# DUAL_CHANNEL_REAY_DRIVER.net
KiCad netlist of a schematic drawn in EAGLE
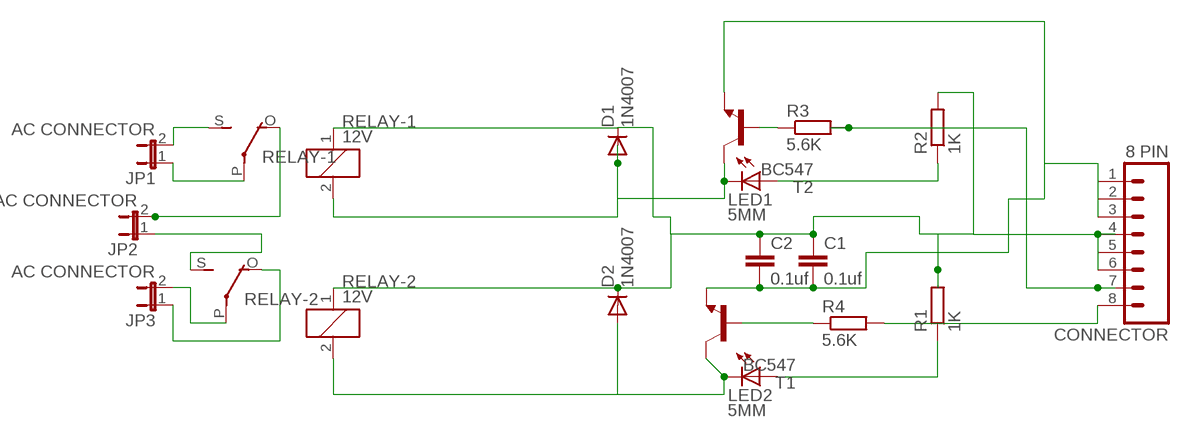
[diagram p0: schematic, sheet 1]

(export (version "E")
  (design (tool "Eeschema 10.0.6"))
  (components
    (comp (ref "C1")
      (value "0.1uf")
      (footprint "eagle-import:C2.5-3")
      (libsource (lib "eagle-import") (part "C2,5-3"))
    )
    (comp (ref "C2")
      (value "0.1uf")
      (footprint "eagle-import:C2.5-3")
      (libsource (lib "eagle-import") (part "C2,5-3"))
    )
    (comp (ref "CONNECTOR")
      (value "8 PIN")
      (footprint "eagle-import:08P")
      (libsource (lib "eagle-import") (part "M08"))
    )
    (comp (ref "D1")
      (value "1N4007")
      (footprint "eagle-import:DO41-10")
      (libsource (lib "eagle-import") (part "1N4004"))
    )
    (comp (ref "D2")
      (value "1N4007")
      (footprint "eagle-import:DO41-10")
      (libsource (lib "eagle-import") (part "1N4004"))
    )
    (comp (ref "JP1")
      (value "AC CONNECTOR")
      (footprint "eagle-import:JP1")
      (libsource (lib "eagle-import") (part "JP1E"))
    )
    (comp (ref "JP2")
      (value "AC CONNECTOR")
      (footprint "eagle-import:JP1")
      (libsource (lib "eagle-import") (part "JP1E"))
    )
    (comp (ref "JP3")
      (value "AC CONNECTOR")
      (footprint "eagle-import:JP1")
      (libsource (lib "eagle-import") (part "JP1E"))
    )
    (comp (ref "LED1")
      (value "5MM")
      (footprint "eagle-import:LED5MM")
      (libsource (lib "eagle-import") (part "LED5MM"))
    )
    (comp (ref "LED2")
      (value "5MM")
      (footprint "eagle-import:LED5MM")
      (libsource (lib "eagle-import") (part "LED5MM"))
    )
    (comp (ref "R1")
      (value "1K")
      (footprint "eagle-import:0204_7")
      (libsource (lib "eagle-import") (part "R-EU_0204/7"))
    )
    (comp (ref "R2")
      (value "1K")
      (footprint "eagle-import:0204_7")
      (libsource (lib "eagle-import") (part "R-EU_0204/7"))
    )
    (comp (ref "R3")
      (value "5.6K")
      (footprint "eagle-import:0204_7")
      (libsource (lib "eagle-import") (part "R-EU_0204/7"))
    )
    (comp (ref "R4")
      (value "5.6K")
      (footprint "eagle-import:0204_7")
      (libsource (lib "eagle-import") (part "R-EU_0204/7"))
    )
    (comp (ref "RELAY-1")
      (value "12V")
      (footprint "eagle-import:G5LE")
      (libsource (lib "eagle-import") (part "G5L"))
    )
    (comp (ref "RELAY-2")
      (value "12V")
      (footprint "eagle-import:G5LE")
      (libsource (lib "eagle-import") (part "G5L"))
    )
    (comp (ref "T1")
      (value "BC547")
      (footprint "eagle-import:TO92")
      (libsource (lib "eagle-import") (part "BC547"))
    )
    (comp (ref "T2")
      (value "BC547")
      (footprint "eagle-import:TO92")
      (libsource (lib "eagle-import") (part "BC547"))
    )
  )
  (nets
    (net (code "1") (name "Net-(C1-Pad1)") (class "Default")
      (node (ref "C1") (pin "1") (pinfunction "1_1") (pintype "passive"))
      (node (ref "C2") (pin "1") (pinfunction "1_1") (pintype "passive"))
      (node (ref "CONNECTOR") (pin "4") (pinfunction "4_4") (pintype "passive"))
      (node (ref "CONNECTOR") (pin "5") (pinfunction "5_5") (pintype "passive"))
      (node (ref "CONNECTOR") (pin "6") (pinfunction "6_6") (pintype "passive"))
      (node (ref "D1") (pin "C") (pinfunction "C_C") (pintype "passive"))
      (node (ref "D2") (pin "C") (pinfunction "C_C") (pintype "passive"))
      (node (ref "R1") (pin "2") (pinfunction "2_2") (pintype "passive"))
      (node (ref "R2") (pin "2") (pinfunction "2_2") (pintype "passive"))
      (node (ref "RELAY-1") (pin "1") (pinfunction "1_1") (pintype "passive"))
      (node (ref "RELAY-2") (pin "1") (pinfunction "1_1") (pintype "passive"))
    )
    (net (code "2") (name "Net-(CONNECTOR-Pad7)") (class "Default")
      (node (ref "CONNECTOR") (pin "7") (pinfunction "7_7") (pintype "passive"))
      (node (ref "R3") (pin "2") (pinfunction "2_2") (pintype "passive"))
    )
    (net (code "3") (name "Net-(CONNECTOR-Pad8)") (class "Default")
      (node (ref "CONNECTOR") (pin "8") (pinfunction "8_8") (pintype "passive"))
      (node (ref "R4") (pin "2") (pinfunction "2_2") (pintype "passive"))
    )
    (net (code "4") (name "Net-(JP1-Pad1)") (class "Default")
      (node (ref "JP1") (pin "1") (pinfunction "1_1") (pintype "passive"))
      (node (ref "RELAY-1") (pin "P") (pinfunction "P_P") (pintype "passive"))
    )
    (net (code "5") (name "Net-(JP1-Pad2)") (class "Default")
      (node (ref "JP1") (pin "2") (pinfunction "2_2") (pintype "passive"))
      (node (ref "RELAY-1") (pin "S") (pinfunction "S_S") (pintype "passive"))
    )
    (net (code "6") (name "Net-(JP2-Pad1)") (class "Default")
      (node (ref "JP2") (pin "1") (pinfunction "1_1") (pintype "passive"))
      (node (ref "RELAY-2") (pin "S") (pinfunction "S_S") (pintype "passive"))
    )
    (net (code "7") (name "Net-(JP2-Pad2)") (class "Default")
      (node (ref "JP2") (pin "2") (pinfunction "2_2") (pintype "passive"))
      (node (ref "RELAY-1") (pin "O") (pinfunction "O_O") (pintype "passive"))
    )
    (net (code "8") (name "Net-(JP3-Pad1)") (class "Default")
      (node (ref "JP3") (pin "1") (pinfunction "1_1") (pintype "passive"))
      (node (ref "RELAY-2") (pin "O") (pinfunction "O_O") (pintype "passive"))
    )
    (net (code "9") (name "Net-(JP3-Pad2)") (class "Default")
      (node (ref "JP3") (pin "2") (pinfunction "2_2") (pintype "passive"))
      (node (ref "RELAY-2") (pin "P") (pinfunction "P_P") (pintype "passive"))
    )
    (net (code "10") (name "Net-(LED1-C)") (class "Default")
      (node (ref "D1") (pin "A") (pinfunction "A_A") (pintype "passive"))
      (node (ref "LED1") (pin "K") (pinfunction "C_K") (pintype "passive"))
      (node (ref "RELAY-1") (pin "2") (pinfunction "2_2") (pintype "passive"))
      (node (ref "T2") (pin "3") (pinfunction "C_3") (pintype "passive"))
    )
    (net (code "11") (name "Net-(LED1-PadA)") (class "Default")
      (node (ref "LED1") (pin "A") (pinfunction "A_A") (pintype "passive"))
      (node (ref "R2") (pin "1") (pinfunction "1_1") (pintype "passive"))
    )
    (net (code "12") (name "Net-(LED2-C)") (class "Default")
      (node (ref "D2") (pin "A") (pinfunction "A_A") (pintype "passive"))
      (node (ref "LED2") (pin "K") (pinfunction "C_K") (pintype "passive"))
      (node (ref "RELAY-2") (pin "2") (pinfunction "2_2") (pintype "passive"))
      (node (ref "T1") (pin "3") (pinfunction "C_3") (pintype "passive"))
    )
    (net (code "13") (name "Net-(LED2-PadA)") (class "Default")
      (node (ref "LED2") (pin "A") (pinfunction "A_A") (pintype "passive"))
      (node (ref "R1") (pin "1") (pinfunction "1_1") (pintype "passive"))
    )
    (net (code "14") (name "Net-(T1-B)") (class "Default")
      (node (ref "R4") (pin "1") (pinfunction "1_1") (pintype "passive"))
      (node (ref "T1") (pin "2") (pinfunction "B_2") (pintype "passive"))
    )
    (net (code "15") (name "Net-(T1-E)") (class "Default")
      (node (ref "C1") (pin "2") (pinfunction "2_2") (pintype "passive"))
      (node (ref "C2") (pin "2") (pinfunction "2_2") (pintype "passive"))
      (node (ref "CONNECTOR") (pin "1") (pinfunction "1_1") (pintype "passive"))
      (node (ref "CONNECTOR") (pin "2") (pinfunction "2_2") (pintype "passive"))
      (node (ref "CONNECTOR") (pin "3") (pinfunction "3_3") (pintype "passive"))
      (node (ref "T1") (pin "1") (pinfunction "E_1") (pintype "passive"))
      (node (ref "T2") (pin "1") (pinfunction "E_1") (pintype "passive"))
    )
    (net (code "16") (name "Net-(T2-B)") (class "Default")
      (node (ref "R3") (pin "1") (pinfunction "1_1") (pintype "passive"))
      (node (ref "T2") (pin "2") (pinfunction "B_2") (pintype "passive"))
    )
  )
)
